# 6draft_onBoard.net
KiCad netlist of a schematic drawn in EAGLE
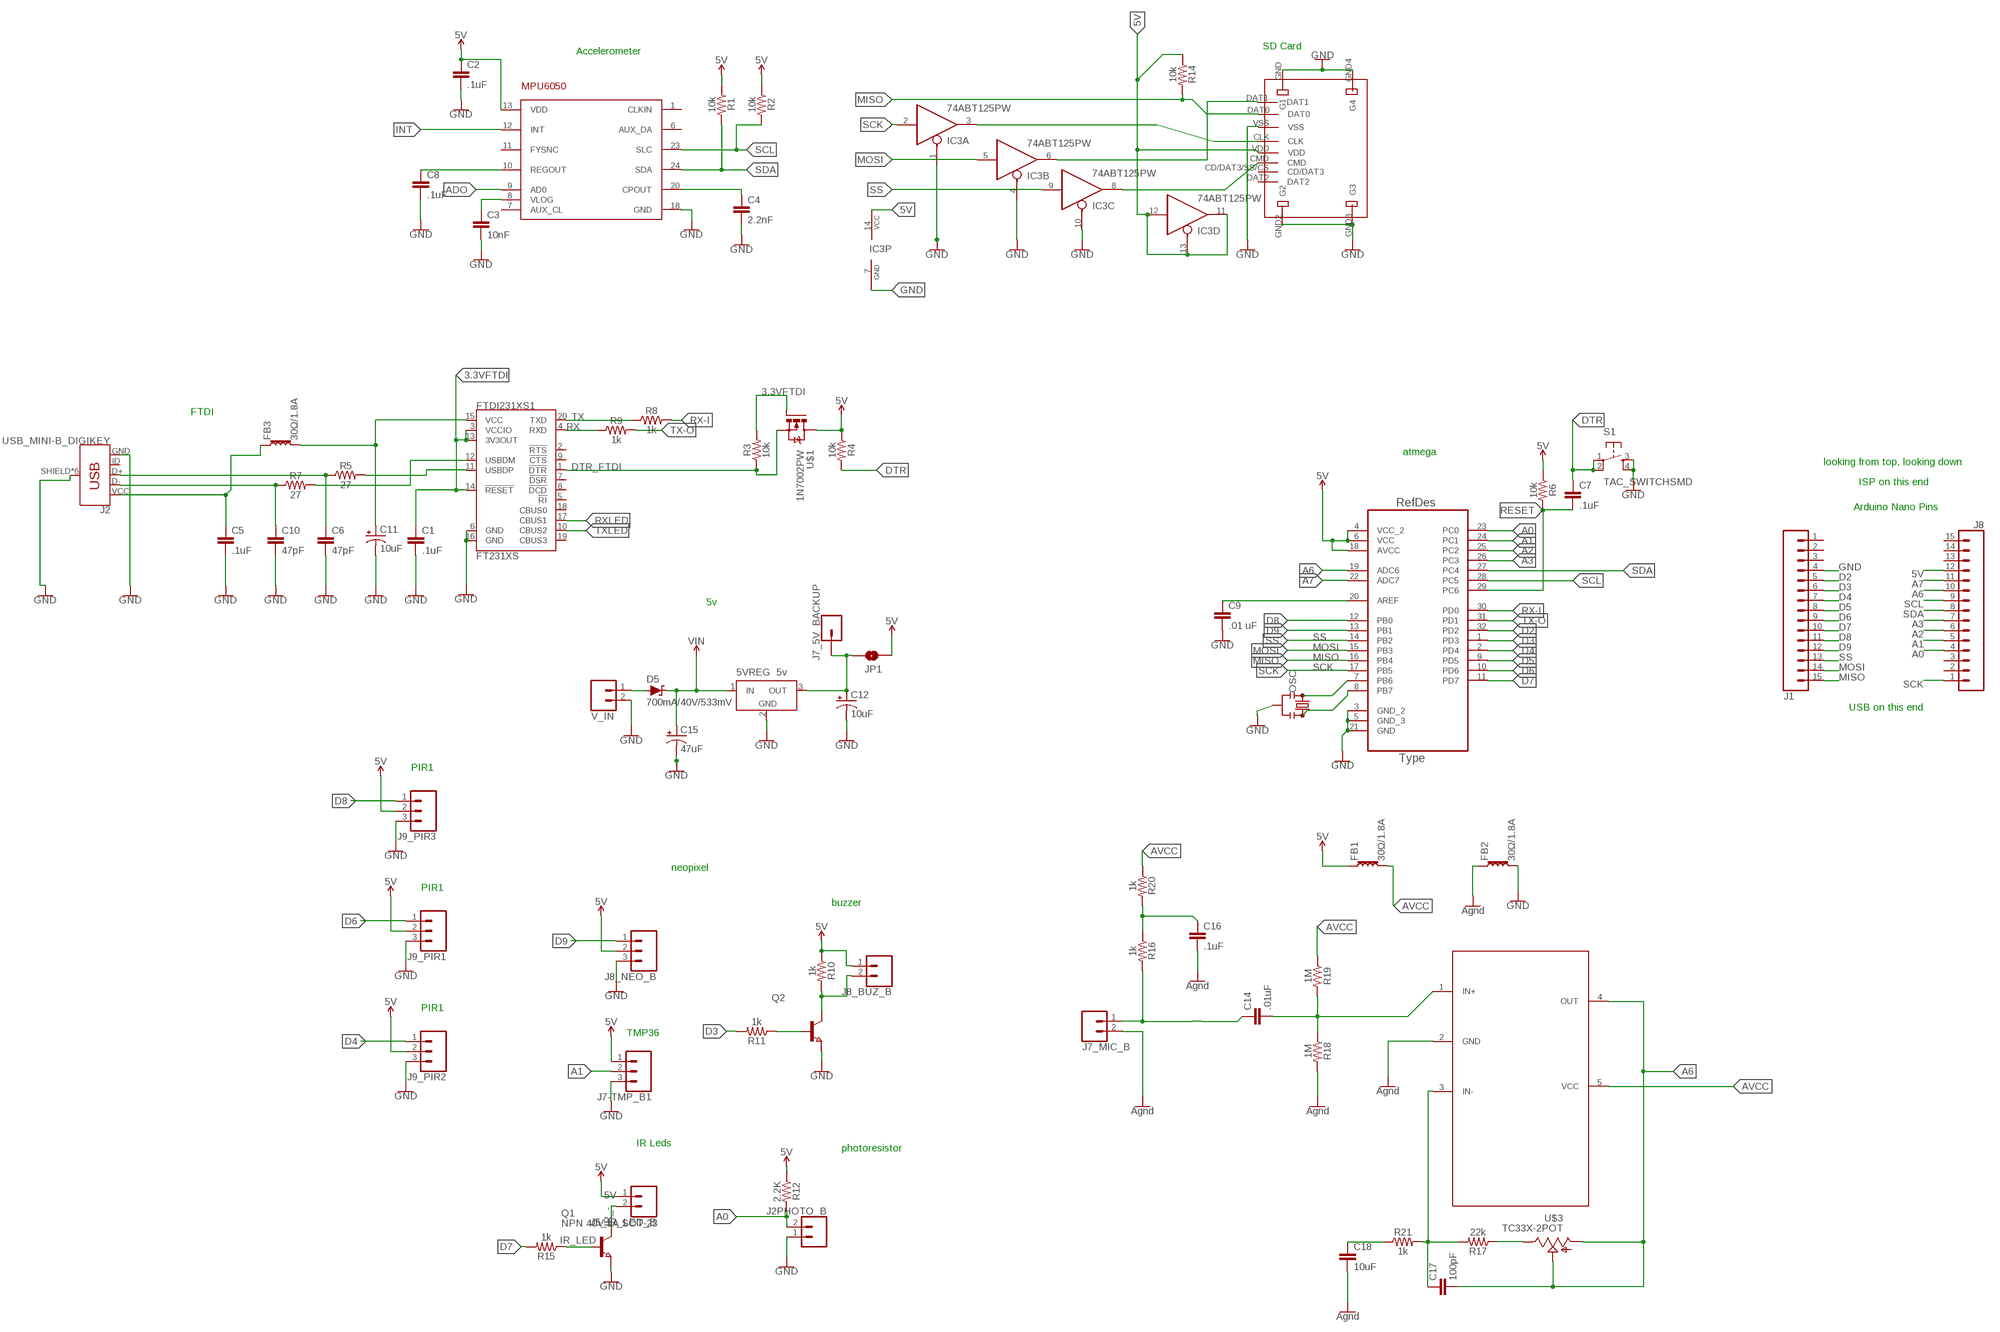
[diagram p0: schematic, sheet 1]

(export (version "E")
  (design (tool "Eeschema 10.0.6"))
  (components
    (comp (ref "5VREG")
      (value "5v")
      (footprint "eagle-import:SOT223")
      (fields (field (name "MPN") "LT1129CST-5#PBF"))
      (libsource (lib "eagle-import") (part "LT1129CST5"))
    )
    (comp (ref "ATMEGA328P-AU")
      (value "ATMEGA328P-AU")
      (footprint "eagle-import:QFP80P900X900X120-32N")
      (libsource (lib "eagle-import") (part "ATMEGA328P-AU"))
    )
    (comp (ref "C1")
      (value ".1uF")
      (footprint "eagle-import:0402-CAP")
      (libsource (lib "eagle-import") (part ".22UF-CER"))
    )
    (comp (ref "C2")
      (value ".1uF")
      (footprint "eagle-import:0402-CAP")
      (libsource (lib "eagle-import") (part ".22UF-CER"))
    )
    (comp (ref "C3")
      (value "10nF")
      (footprint "eagle-import:0402-CAP")
      (libsource (lib "eagle-import") (part ".22UF-CER"))
    )
    (comp (ref "C4")
      (value "2.2nF")
      (footprint "eagle-import:0402-CAP")
      (libsource (lib "eagle-import") (part ".22UF-CER"))
    )
    (comp (ref "C5")
      (value ".1uF")
      (footprint "eagle-import:0402-CAP")
      (libsource (lib "eagle-import") (part ".22UF-CER"))
    )
    (comp (ref "C6")
      (value "47pF")
      (footprint "eagle-import:0402-CAP")
      (libsource (lib "eagle-import") (part ".22UF-CER"))
    )
    (comp (ref "C7")
      (value ".1uF")
      (footprint "eagle-import:0402-CAP")
      (libsource (lib "eagle-import") (part ".22UF-CER"))
    )
    (comp (ref "C8")
      (value ".1uF")
      (footprint "eagle-import:0402-CAP")
      (libsource (lib "eagle-import") (part ".22UF-CER"))
    )
    (comp (ref "C9")
      (value ".01 uF")
      (footprint "eagle-import:0402-CAP")
      (libsource (lib "eagle-import") (part ".22UF-CER"))
    )
    (comp (ref "C10")
      (value "47pF")
      (footprint "eagle-import:0402-CAP")
      (libsource (lib "eagle-import") (part ".22UF-CER"))
    )
    (comp (ref "C11")
      (value "10uF")
      (footprint "eagle-import:EIA3216")
      (libsource (lib "eagle-import") (part "10UF-TANT"))
    )
    (comp (ref "C12")
      (value "10uF")
      (footprint "eagle-import:EIA3216")
      (libsource (lib "eagle-import") (part "10UF-TANT"))
    )
    (comp (ref "C14")
      (value ".01uF")
      (footprint "eagle-import:0402-CAP")
      (libsource (lib "eagle-import") (part ".22UF-CER"))
    )
    (comp (ref "C15")
      (value "47uF")
      (footprint "eagle-import:EIA3216")
      (libsource (lib "eagle-import") (part "10UF-TANT"))
    )
    (comp (ref "C16")
      (value ".1uF")
      (footprint "eagle-import:0402-CAP")
      (libsource (lib "eagle-import") (part ".22UF-CER"))
    )
    (comp (ref "C17")
      (value "100pF")
      (footprint "eagle-import:0402-CAP")
      (libsource (lib "eagle-import") (part ".22UF-CER"))
    )
    (comp (ref "C18")
      (value "10uF")
      (footprint "eagle-import:0402-CAP")
      (libsource (lib "eagle-import") (part ".22UF-CER"))
    )
    (comp (ref "D5")
      (value "700mA/40V/533mV")
      (footprint "eagle-import:SOT23-3")
      (libsource (lib "eagle-import") (part "DIODE-SCHOTTKY-ZLLS500"))
    )
    (comp (ref "FB1")
      (value "30Ω/1.8A")
      (footprint "eagle-import:0603")
      (libsource (lib "eagle-import") (part "FERRITE_BEAD-0603"))
    )
    (comp (ref "FB2")
      (value "30Ω/1.8A")
      (footprint "eagle-import:0603")
      (libsource (lib "eagle-import") (part "FERRITE_BEAD-0603"))
    )
    (comp (ref "FB3")
      (value "30Ω/1.8A")
      (footprint "eagle-import:0603")
      (libsource (lib "eagle-import") (part "FERRITE_BEAD-0603"))
    )
    (comp (ref "FTDI231XS1")
      (value "FT231XS")
      (footprint "eagle-import:SSOP20_L")
      (libsource (lib "eagle-import") (part "FT231XS"))
    )
    (comp (ref "IC3")
      (value "74ABT125PW")
      (footprint "eagle-import:TSSOP14")
      (libsource (lib "eagle-import") (part "74125PWABT"))
    )
    (comp (ref "IC4")
      (value "MAX4466KS")
      (footprint "eagle-import:SC70-5")
      (libsource (lib "eagle-import") (part "MAX4466KS"))
    )
    (comp (ref "J1")
      (value "CONN_15")
      (footprint "eagle-import:1X15")
      (libsource (lib "eagle-import") (part "CONN_15"))
    )
    (comp (ref "J2")
      (value "USB_MINI-B_DIGIKEY")
      (footprint "eagle-import:MICRO-USB-DIGIKEY-FCI2")
      (libsource (lib "eagle-import") (part "USB_MINI-B_DIGIKEY"))
    )
    (comp (ref "J2PHOTO_B")
      (value "CONN_02LOCK")
      (footprint "eagle-import:1X02_LOCK")
      (libsource (lib "eagle-import") (part "CONN_02LOCK"))
    )
    (comp (ref "J5_IR_LED_B")
      (value "CONN_02LOCK")
      (footprint "eagle-import:1X02_LOCK")
      (libsource (lib "eagle-import") (part "CONN_02LOCK"))
    )
    (comp (ref "J7-TMP_B1")
      (value "CONN_03")
      (footprint "eagle-import:1X03")
      (libsource (lib "eagle-import") (part "CONN_03"))
    )
    (comp (ref "J7_5V_BACKUP")
      (value "CONN_01")
      (footprint "eagle-import:1X01")
      (libsource (lib "eagle-import") (part "CONN_01"))
    )
    (comp (ref "J7_MIC_B")
      (value "CONN_02LOCK")
      (footprint "eagle-import:1X02_LOCK")
      (libsource (lib "eagle-import") (part "CONN_02LOCK"))
    )
    (comp (ref "J8")
      (value "CONN_15")
      (footprint "eagle-import:1X15")
      (libsource (lib "eagle-import") (part "CONN_15"))
    )
    (comp (ref "J8_BUZ_B")
      (value "CONN_02LOCK")
      (footprint "eagle-import:1X02_LOCK")
      (libsource (lib "eagle-import") (part "CONN_02LOCK"))
    )
    (comp (ref "J8_NEO_B")
      (value "CONN_03")
      (footprint "eagle-import:1X03")
      (libsource (lib "eagle-import") (part "CONN_03"))
    )
    (comp (ref "J9_PIR1")
      (value "CONN_03")
      (footprint "eagle-import:1X03")
      (libsource (lib "eagle-import") (part "CONN_03"))
    )
    (comp (ref "J9_PIR2")
      (value "CONN_03")
      (footprint "eagle-import:1X03")
      (libsource (lib "eagle-import") (part "CONN_03"))
    )
    (comp (ref "J9_PIR3")
      (value "CONN_03")
      (footprint "eagle-import:1X03")
      (libsource (lib "eagle-import") (part "CONN_03"))
    )
    (comp (ref "JP1")
      (value "JUMPER-SMT_2_NO_NO-SILK_ROUND")
      (footprint "eagle-import:SMT-JUMPER_2_NO_NO-SILK_ROUND")
      (libsource (lib "eagle-import") (part "JUMPER-SMT_2_NO_NO-SILK_ROUND"))
    )
    (comp (ref "MPU6050")
      (value "MPU-6050")
      (footprint "eagle-import:QFN24-4X4")
      (libsource (lib "eagle-import") (part "MPU-6050"))
    )
    (comp (ref "OSC")
      (value "RESONATORSMD-3.2X1.3")
      (footprint "eagle-import:RESONATOR-SMD-3.2X1.3")
      (libsource (lib "eagle-import") (part "RESONATORSMD-3.2X1.3"))
    )
    (comp (ref "Q1")
      (value "NPN 40V 1A SOT-23")
      (footprint "eagle-import:SOT23")
      (libsource (lib "eagle-import") (part "NPN-TRANSISTOR_SOT23"))
    )
    (comp (ref "Q2")
      (value "NPN-TRANSISTOR_SOT23")
      (footprint "eagle-import:SOT23")
      (libsource (lib "eagle-import") (part "NPN-TRANSISTOR_SOT23"))
    )
    (comp (ref "R1")
      (value "10k")
      (footprint "eagle-import:0603")
      (libsource (lib "eagle-import") (part "0.05OHM-0603-1/5W-1%"))
    )
    (comp (ref "R2")
      (value "10k")
      (footprint "eagle-import:0603")
      (libsource (lib "eagle-import") (part "0.05OHM-0603-1/5W-1%"))
    )
    (comp (ref "R3")
      (value "10k")
      (footprint "eagle-import:0603")
      (libsource (lib "eagle-import") (part "0.05OHM-0603-1/5W-1%"))
    )
    (comp (ref "R4")
      (value "10k")
      (footprint "eagle-import:0603")
      (libsource (lib "eagle-import") (part "0.05OHM-0603-1/5W-1%"))
    )
    (comp (ref "R5")
      (value "27")
      (footprint "eagle-import:0603")
      (libsource (lib "eagle-import") (part "0.05OHM-0603-1/5W-1%"))
    )
    (comp (ref "R6")
      (value "10k")
      (footprint "eagle-import:0603")
      (libsource (lib "eagle-import") (part "0.05OHM-0603-1/5W-1%"))
    )
    (comp (ref "R7")
      (value "27")
      (footprint "eagle-import:0603")
      (libsource (lib "eagle-import") (part "0.05OHM-0603-1/5W-1%"))
    )
    (comp (ref "R8")
      (value "1k")
      (footprint "eagle-import:0603")
      (libsource (lib "eagle-import") (part "0.05OHM-0603-1/5W-1%"))
    )
    (comp (ref "R9")
      (value "1k")
      (footprint "eagle-import:0603")
      (libsource (lib "eagle-import") (part "0.05OHM-0603-1/5W-1%"))
    )
    (comp (ref "R10")
      (value "1k")
      (footprint "eagle-import:0603")
      (libsource (lib "eagle-import") (part "0.05OHM-0603-1/5W-1%"))
    )
    (comp (ref "R11")
      (value "1k")
      (footprint "eagle-import:0603")
      (libsource (lib "eagle-import") (part "0.05OHM-0603-1/5W-1%"))
    )
    (comp (ref "R12")
      (value "2.2K")
      (footprint "eagle-import:0603")
      (libsource (lib "eagle-import") (part "0.05OHM-0603-1/5W-1%"))
    )
    (comp (ref "R14")
      (value "10k")
      (footprint "eagle-import:0603")
      (libsource (lib "eagle-import") (part "0.05OHM-0603-1/5W-1%"))
    )
    (comp (ref "R15")
      (value "1k")
      (footprint "eagle-import:0603")
      (libsource (lib "eagle-import") (part "0.05OHM-0603-1/5W-1%"))
    )
    (comp (ref "R16")
      (value "1k")
      (footprint "eagle-import:0603")
      (libsource (lib "eagle-import") (part "0.05OHM-0603-1/5W-1%"))
    )
    (comp (ref "R17")
      (value "22k")
      (footprint "eagle-import:0603")
      (libsource (lib "eagle-import") (part "0.05OHM-0603-1/5W-1%"))
    )
    (comp (ref "R18")
      (value "1M")
      (footprint "eagle-import:0603")
      (libsource (lib "eagle-import") (part "0.05OHM-0603-1/5W-1%"))
    )
    (comp (ref "R19")
      (value "1M")
      (footprint "eagle-import:0603")
      (libsource (lib "eagle-import") (part "0.05OHM-0603-1/5W-1%"))
    )
    (comp (ref "R20")
      (value "1k")
      (footprint "eagle-import:0603")
      (libsource (lib "eagle-import") (part "0.05OHM-0603-1/5W-1%"))
    )
    (comp (ref "R21")
      (value "1k")
      (footprint "eagle-import:0603")
      (libsource (lib "eagle-import") (part "0.05OHM-0603-1/5W-1%"))
    )
    (comp (ref "S1")
      (value "TAC_SWITCHSMD")
      (footprint "eagle-import:TACTILE-SWITCH-SMD")
      (libsource (lib "eagle-import") (part "TAC_SWITCHSMD"))
    )
    (comp (ref "U$1")
      (value "1N7002PW")
      (footprint "eagle-import:SOT323W_INFINEON")
      (libsource (lib "eagle-import") (part "1N7002PW"))
    )
    (comp (ref "U$2")
      (value "WM6698TR-ND_MICROSD")
      (footprint "eagle-import:MICROSD2")
      (libsource (lib "eagle-import") (part "WM6698TR-ND_MICROSD"))
    )
    (comp (ref "U$3")
      (value "TC33X-2POT")
      (footprint "eagle-import:TC33X-2")
      (libsource (lib "eagle-import") (part "TC33X-2POT"))
    )
    (comp (ref "V_IN")
      (value "CONN_02LOCK")
      (footprint "eagle-import:1X02_LOCK")
      (libsource (lib "eagle-import") (part "CONN_02LOCK"))
    )
  )
  (nets
    (net (code "1") (name "/DTR_FTDI") (class "Default")
      (node (ref "FTDI231XS1") (pin "1") (pinfunction "~{DTR}_1") (pintype "bidirectional"))
      (node (ref "R3") (pin "1") (pinfunction "1_1") (pintype "passive"))
      (node (ref "U$1") (pin "2") (pinfunction "S_2") (pintype "passive"))
    )
    (net (code "2") (name "/IR_-") (class "Default")
      (node (ref "J5_IR_LED_B") (pin "2") (pinfunction "2_2") (pintype "passive"))
      (node (ref "Q1") (pin "3") (pinfunction "C_3") (pintype "passive"))
    )
    (net (code "3") (name "/IR_LED") (class "Default")
      (node (ref "Q1") (pin "1") (pinfunction "B_1") (pintype "passive"))
      (node (ref "R15") (pin "1") (pinfunction "1_1") (pintype "passive"))
    )
    (net (code "4") (name "/RX") (class "Default")
      (node (ref "FTDI231XS1") (pin "4") (pinfunction "RXD_4") (pintype "bidirectional"))
      (node (ref "R9") (pin "1") (pinfunction "1_1") (pintype "passive"))
    )
    (net (code "5") (name "/TX") (class "Default")
      (node (ref "FTDI231XS1") (pin "20") (pinfunction "TXD_20") (pintype "bidirectional"))
      (node (ref "R8") (pin "1") (pinfunction "1_1") (pintype "passive"))
    )
    (net (code "6") (name "/VUSB") (class "Default")
      (node (ref "C11") (pin "A") (pinfunction "+_A") (pintype "passive"))
      (node (ref "C5") (pin "1") (pinfunction "1_1") (pintype "passive"))
      (node (ref "FB3") (pin "1") (pinfunction "1_1") (pintype "passive"))
      (node (ref "FB3") (pin "2") (pinfunction "2_2") (pintype "passive"))
      (node (ref "FTDI231XS1") (pin "15") (pinfunction "VCC_15") (pintype "bidirectional"))
      (node (ref "J2") (pin "VCC") (pinfunction "VBUS_VCC") (pintype "power_in"))
    )
    (net (code "7") (name "3.3VFTDI") (class "Default")
      (node (ref "C1") (pin "1") (pinfunction "1_1") (pintype "passive"))
      (node (ref "FTDI231XS1") (pin "13") (pinfunction "3V3OUT_13") (pintype "bidirectional"))
      (node (ref "FTDI231XS1") (pin "14") (pinfunction "~{RESET}_14") (pintype "bidirectional"))
      (node (ref "FTDI231XS1") (pin "3") (pinfunction "VCCIO_3") (pintype "bidirectional"))
      (node (ref "R3") (pin "2") (pinfunction "2_2") (pintype "passive"))
      (node (ref "U$1") (pin "1") (pinfunction "G_1") (pintype "passive"))
    )
    (net (code "8") (name "5V") (class "Default")
      (node (ref "ATMEGA328P-AU") (pin "18") (pinfunction "AVCC_18") (pintype "power_in"))
      (node (ref "ATMEGA328P-AU") (pin "4") (pinfunction "VCC_2_4") (pintype "power_in"))
      (node (ref "ATMEGA328P-AU") (pin "6") (pinfunction "VCC_6") (pintype "power_in"))
      (node (ref "C2") (pin "1") (pinfunction "1_1") (pintype "passive"))
      (node (ref "FB1") (pin "1") (pinfunction "1_1") (pintype "passive"))
      (node (ref "IC3") (pin "11") (pinfunction "O_11") (pintype "tri_state"))
      (node (ref "IC3") (pin "12") (pinfunction "I_12") (pintype "input"))
      (node (ref "IC3") (pin "13") (pinfunction "OE_13") (pintype "input"))
      (node (ref "IC3") (pin "14") (pinfunction "VCC_14") (pintype "power_in"))
      (node (ref "J5_IR_LED_B") (pin "1") (pinfunction "1_1") (pintype "passive"))
      (node (ref "J7-TMP_B1") (pin "1") (pinfunction "1_1") (pintype "passive"))
      (node (ref "J8") (pin "12") (pinfunction "12_12") (pintype "passive"))
      (node (ref "J8_BUZ_B") (pin "1") (pinfunction "1_1") (pintype "passive"))
      (node (ref "J8_NEO_B") (pin "2") (pinfunction "2_2") (pintype "passive"))
      (node (ref "J9_PIR1") (pin "2") (pinfunction "2_2") (pintype "passive"))
      (node (ref "J9_PIR2") (pin "2") (pinfunction "2_2") (pintype "passive"))
      (node (ref "J9_PIR3") (pin "2") (pinfunction "2_2") (pintype "passive"))
      (node (ref "JP1") (pin "1") (pinfunction "1_1") (pintype "passive"))
      (node (ref "MPU6050") (pin "13") (pinfunction "VDD_13") (pintype "bidirectional"))
      (node (ref "R1") (pin "1") (pinfunction "1_1") (pintype "passive"))
      (node (ref "R10") (pin "1") (pinfunction "1_1") (pintype "passive"))
      (node (ref "R12") (pin "1") (pinfunction "1_1") (pintype "passive"))
      (node (ref "R14") (pin "1") (pinfunction "1_1") (pintype "passive"))
      (node (ref "R2") (pin "1") (pinfunction "1_1") (pintype "passive"))
      (node (ref "R4") (pin "1") (pinfunction "1_1") (pintype "passive"))
      (node (ref "R6") (pin "1") (pinfunction "1_1") (pintype "passive"))
      (node (ref "U$1") (pin "3") (pinfunction "D_3") (pintype "passive"))
      (node (ref "U$2") (pin "VDD") (pinfunction "VDD_VDD") (pintype "bidirectional"))
    )
    (net (code "9") (name "A0") (class "Default")
      (node (ref "ATMEGA328P-AU") (pin "23") (pinfunction "PC0_23") (pintype "bidirectional"))
      (node (ref "J2PHOTO_B") (pin "2") (pinfunction "2_2") (pintype "passive"))
      (node (ref "J8") (pin "4") (pinfunction "4_4") (pintype "passive"))
      (node (ref "R12") (pin "2") (pinfunction "2_2") (pintype "passive"))
    )
    (net (code "10") (name "A1") (class "Default")
      (node (ref "ATMEGA328P-AU") (pin "24") (pinfunction "PC1_24") (pintype "bidirectional"))
      (node (ref "J7-TMP_B1") (pin "2") (pinfunction "2_2") (pintype "passive"))
      (node (ref "J8") (pin "5") (pinfunction "5_5") (pintype "passive"))
    )
    (net (code "11") (name "A2") (class "Default")
      (node (ref "ATMEGA328P-AU") (pin "25") (pinfunction "PC2_25") (pintype "bidirectional"))
      (node (ref "J8") (pin "6") (pinfunction "6_6") (pintype "passive"))
    )
    (net (code "12") (name "A3") (class "Default")
      (node (ref "ATMEGA328P-AU") (pin "26") (pinfunction "PC3_26") (pintype "bidirectional"))
      (node (ref "J8") (pin "7") (pinfunction "7_7") (pintype "passive"))
    )
    (net (code "13") (name "A6") (class "Default")
      (node (ref "ATMEGA328P-AU") (pin "19") (pinfunction "ADC6_19") (pintype "input"))
      (node (ref "C17") (pin "2") (pinfunction "2_2") (pintype "passive"))
      (node (ref "IC4") (pin "4") (pinfunction "OUT_4") (pintype "bidirectional"))
      (node (ref "J8") (pin "10") (pinfunction "10_10") (pintype "passive"))
      (node (ref "U$3") (pin "2") (pinfunction "2_2") (pintype "passive"))
      (node (ref "U$3") (pin "3") (pinfunction "3_3") (pintype "passive"))
    )
    (net (code "14") (name "A7") (class "Default")
      (node (ref "ATMEGA328P-AU") (pin "22") (pinfunction "ADC7_22") (pintype "input"))
      (node (ref "J8") (pin "11") (pinfunction "11_11") (pintype "passive"))
    )
    (net (code "15") (name "ADO") (class "Default")
      (node (ref "MPU6050") (pin "9") (pinfunction "AD0_9") (pintype "bidirectional"))
    )
    (net (code "16") (name "AVCC") (class "Default")
      (node (ref "FB1") (pin "2") (pinfunction "2_2") (pintype "passive"))
      (node (ref "IC4") (pin "5") (pinfunction "VCC_5") (pintype "bidirectional"))
      (node (ref "R19") (pin "1") (pinfunction "1_1") (pintype "passive"))
      (node (ref "R20") (pin "1") (pinfunction "1_1") (pintype "passive"))
    )
    (net (code "17") (name "D2") (class "Default")
      (node (ref "ATMEGA328P-AU") (pin "32") (pinfunction "PD2_32") (pintype "bidirectional"))
      (node (ref "J1") (pin "5") (pinfunction "5_5") (pintype "passive"))
    )
    (net (code "18") (name "D3") (class "Default")
      (node (ref "ATMEGA328P-AU") (pin "1") (pinfunction "PD3_1") (pintype "bidirectional"))
      (node (ref "J1") (pin "6") (pinfunction "6_6") (pintype "passive"))
      (node (ref "R11") (pin "2") (pinfunction "2_2") (pintype "passive"))
    )
    (net (code "19") (name "D4") (class "Default")
      (node (ref "ATMEGA328P-AU") (pin "2") (pinfunction "PD4_2") (pintype "bidirectional"))
      (node (ref "J1") (pin "7") (pinfunction "7_7") (pintype "passive"))
      (node (ref "J9_PIR2") (pin "1") (pinfunction "1_1") (pintype "passive"))
    )
    (net (code "20") (name "D5") (class "Default")
      (node (ref "ATMEGA328P-AU") (pin "9") (pinfunction "PD5_9") (pintype "bidirectional"))
      (node (ref "J1") (pin "8") (pinfunction "8_8") (pintype "passive"))
    )
    (net (code "21") (name "D6") (class "Default")
      (node (ref "ATMEGA328P-AU") (pin "10") (pinfunction "PD6_10") (pintype "bidirectional"))
      (node (ref "J1") (pin "9") (pinfunction "9_9") (pintype "passive"))
      (node (ref "J9_PIR1") (pin "1") (pinfunction "1_1") (pintype "passive"))
    )
    (net (code "22") (name "D7") (class "Default")
      (node (ref "ATMEGA328P-AU") (pin "11") (pinfunction "PD7_11") (pintype "bidirectional"))
      (node (ref "J1") (pin "10") (pinfunction "10_10") (pintype "passive"))
      (node (ref "R15") (pin "2") (pinfunction "2_2") (pintype "passive"))
    )
    (net (code "23") (name "D8") (class "Default")
      (node (ref "ATMEGA328P-AU") (pin "12") (pinfunction "PB0_12") (pintype "bidirectional"))
      (node (ref "J1") (pin "11") (pinfunction "11_11") (pintype "passive"))
      (node (ref "J9_PIR3") (pin "1") (pinfunction "1_1") (pintype "passive"))
    )
    (net (code "24") (name "D9") (class "Default")
      (node (ref "ATMEGA328P-AU") (pin "13") (pinfunction "PB1_13") (pintype "bidirectional"))
      (node (ref "J1") (pin "12") (pinfunction "12_12") (pintype "passive"))
      (node (ref "J8_NEO_B") (pin "1") (pinfunction "1_1") (pintype "passive"))
    )
    (net (code "25") (name "DTR") (class "Default")
      (node (ref "C7") (pin "1") (pinfunction "1_1") (pintype "passive"))
      (node (ref "R4") (pin "2") (pinfunction "2_2") (pintype "passive"))
      (node (ref "S1") (pin "1") (pinfunction "1_1") (pintype "passive"))
      (node (ref "S1") (pin "2") (pinfunction "2_2") (pintype "passive"))
    )
    (net (code "26") (name "GND") (class "Default")
      (node (ref "5VREG") (pin "2") (pinfunction "GND_2") (pintype "power_in"))
      (node (ref "ATMEGA328P-AU") (pin "21") (pinfunction "GND_21") (pintype "passive"))
      (node (ref "ATMEGA328P-AU") (pin "3") (pinfunction "GND_2_3") (pintype "passive"))
      (node (ref "ATMEGA328P-AU") (pin "5") (pinfunction "GND_3_5") (pintype "passive"))
      (node (ref "C1") (pin "2") (pinfunction "2_2") (pintype "passive"))
      (node (ref "C10") (pin "2") (pinfunction "2_2") (pintype "passive"))
      (node (ref "C11") (pin "C") (pinfunction "-_C") (pintype "passive"))
      (node (ref "C12") (pin "C") (pinfunction "-_C") (pintype "passive"))
      (node (ref "C15") (pin "C") (pinfunction "-_C") (pintype "passive"))
      (node (ref "C16") (pin "2") (pinfunction "2_2") (pintype "passive"))
      (node (ref "C18") (pin "2") (pinfunction "2_2") (pintype "passive"))
      (node (ref "C2") (pin "2") (pinfunction "2_2") (pintype "passive"))
      (node (ref "C3") (pin "2") (pinfunction "2_2") (pintype "passive"))
      (node (ref "C4") (pin "2") (pinfunction "2_2") (pintype "passive"))
      (node (ref "C5") (pin "2") (pinfunction "2_2") (pintype "passive"))
      (node (ref "C6") (pin "2") (pinfunction "2_2") (pintype "passive"))
      (node (ref "C8") (pin "2") (pinfunction "2_2") (pintype "passive"))
      (node (ref "C9") (pin "2") (pinfunction "2_2") (pintype "passive"))
      (node (ref "FB2") (pin "1") (pinfunction "1_1") (pintype "passive"))
      (node (ref "FB2") (pin "2") (pinfunction "2_2") (pintype "passive"))
      (node (ref "FTDI231XS1") (pin "16") (pinfunction "GND_16") (pintype "bidirectional"))
      (node (ref "FTDI231XS1") (pin "6") (pinfunction "GND_6") (pintype "bidirectional"))
      (node (ref "IC3") (pin "1") (pinfunction "OE_1") (pintype "input"))
      (node (ref "IC3") (pin "10") (pinfunction "OE_10") (pintype "input"))
      (node (ref "IC3") (pin "4") (pinfunction "OE_4") (pintype "input"))
      (node (ref "IC3") (pin "7") (pinfunction "GND_7") (pintype "power_in"))
      (node (ref "IC4") (pin "2") (pinfunction "GND_2") (pintype "bidirectional"))
      (node (ref "J1") (pin "4") (pinfunction "4_4") (pintype "passive"))
      (node (ref "J2") (pin "GND") (pinfunction "GND_GND") (pintype "power_in"))
      (node (ref "J2") (pin "SHIELD") (pinfunction "SHIELD_SHIELD") (pintype "bidirectional"))
      (node (ref "J2") (pin "SHIELD1") (pinfunction "SHIELD_SHIELD1") (pintype "bidirectional"))
      (node (ref "J2") (pin "SHIELD2") (pinfunction "SHIELD_SHIELD2") (pintype "bidirectional"))
      (node (ref "J2") (pin "SHIELD3") (pinfunction "SHIELD_SHIELD3") (pintype "bidirectional"))
      (node (ref "J2") (pin "SHIELD4") (pinfunction "SHIELD_SHIELD4") (pintype "bidirectional"))
      (node (ref "J2") (pin "SHIELD5") (pinfunction "SHIELD_SHIELD5") (pintype "bidirectional"))
      (node (ref "J2PHOTO_B") (pin "1") (pinfunction "1_1") (pintype "passive"))
      (node (ref "J7-TMP_B1") (pin "3") (pinfunction "3_3") (pintype "passive"))
      (node (ref "J7_MIC_B") (pin "2") (pinfunction "2_2") (pintype "passive"))
      (node (ref "J8_NEO_B") (pin "3") (pinfunction "3_3") (pintype "passive"))
      (node (ref "J9_PIR1") (pin "3") (pinfunction "3_3") (pintype "passive"))
      (node (ref "J9_PIR2") (pin "3") (pinfunction "3_3") (pintype "passive"))
      (node (ref "J9_PIR3") (pin "3") (pinfunction "3_3") (pintype "passive"))
      (node (ref "MPU6050") (pin "18") (pinfunction "GND_18") (pintype "bidirectional"))
      (node (ref "OSC") (pin "2") (pinfunction "2_2") (pintype "passive"))
      (node (ref "Q1") (pin "2") (pinfunction "E_2") (pintype "passive"))
      (node (ref "Q2") (pin "2") (pinfunction "E_2") (pintype "passive"))
      (node (ref "R18") (pin "2") (pinfunction "2_2") (pintype "passive"))
      (node (ref "S1") (pin "3") (pinfunction "3_3") (pintype "passive"))
      (node (ref "S1") (pin "4") (pinfunction "4_4") (pintype "passive"))
      (node (ref "U$2") (pin "GND") (pinfunction "G1_GND") (pintype "bidirectional"))
      (node (ref "U$2") (pin "GND2") (pinfunction "G2_GND2") (pintype "bidirectional"))
      (node (ref "U$2") (pin "GND3") (pinfunction "G3_GND3") (pintype "bidirectional"))
      (node (ref "U$2") (pin "GND4") (pinfunction "G4_GND4") (pintype "bidirectional"))
      (node (ref "U$2") (pin "VSS") (pinfunction "VSS_VSS") (pintype "bidirectional"))
      (node (ref "V_IN") (pin "2") (pinfunction "2_2") (pintype "passive"))
    )
    (net (code "27") (name "INT") (class "Default")
      (node (ref "MPU6050") (pin "12") (pinfunction "INT_12") (pintype "bidirectional"))
    )
    (net (code "28") (name "MISO") (class "Default")
      (node (ref "ATMEGA328P-AU") (pin "16") (pinfunction "PB4_16") (pintype "bidirectional"))
      (node (ref "J1") (pin "15") (pinfunction "15_15") (pintype "passive"))
      (node (ref "R14") (pin "2") (pinfunction "2_2") (pintype "passive"))
      (node (ref "U$2") (pin "DAT0") (pinfunction "DAT0_DAT0") (pintype "bidirectional"))
    )
    (net (code "29") (name "MOSI") (class "Default")
      (node (ref "ATMEGA328P-AU") (pin "15") (pinfunction "PB3_15") (pintype "bidirectional"))
      (node (ref "IC3") (pin "5") (pinfunction "I_5") (pintype "input"))
      (node (ref "J1") (pin "14") (pinfunction "14_14") (pintype "passive"))
    )
    (net (code "30") (name "Net-(5VREGA-OUT)") (class "Default")
      (node (ref "5VREG") (pin "3") (pinfunction "OUT_3") (pintype "output"))
      (node (ref "C12") (pin "A") (pinfunction "+_A") (pintype "passive"))
      (node (ref "J7_5V_BACKUP") (pin "1") (pinfunction "1_1") (pintype "passive"))
      (node (ref "JP1") (pin "2") (pinfunction "2_2") (pintype "passive"))
    )
    (net (code "31") (name "Net-(ATMEGA328P-AU-AREF)") (class "Default")
      (node (ref "ATMEGA328P-AU") (pin "20") (pinfunction "AREF_20") (pintype "input"))
      (node (ref "C9") (pin "1") (pinfunction "1_1") (pintype "passive"))
    )
    (net (code "32") (name "Net-(ATMEGA328P-AU-PB6)") (class "Default")
      (node (ref "ATMEGA328P-AU") (pin "7") (pinfunction "PB6_7") (pintype "bidirectional"))
      (node (ref "OSC") (pin "1") (pinfunction "1_1") (pintype "passive"))
    )
    (net (code "33") (name "Net-(ATMEGA328P-AU-PB7)") (class "Default")
      (node (ref "ATMEGA328P-AU") (pin "8") (pinfunction "PB7_8") (pintype "bidirectional"))
      (node (ref "OSC") (pin "3") (pinfunction "3_3") (pintype "passive"))
    )
    (net (code "34") (name "Net-(C6-Pad1)") (class "Default")
      (node (ref "C6") (pin "1") (pinfunction "1_1") (pintype "passive"))
      (node (ref "J2") (pin "D+") (pinfunction "D+_D+") (pintype "bidirectional"))
      (node (ref "R5") (pin "1") (pinfunction "1_1") (pintype "passive"))
    )
    (net (code "35") (name "Net-(C10-Pad1)") (class "Default")
      (node (ref "C10") (pin "1") (pinfunction "1_1") (pintype "passive"))
      (node (ref "J2") (pin "D-") (pinfunction "D-_D-") (pintype "bidirectional"))
      (node (ref "R7") (pin "1") (pinfunction "1_1") (pintype "passive"))
    )
    (net (code "36") (name "Net-(C14-Pad1)") (class "Default")
      (node (ref "C14") (pin "1") (pinfunction "1_1") (pintype "passive"))
      (node (ref "J7_MIC_B") (pin "1") (pinfunction "1_1") (pintype "passive"))
      (node (ref "R16") (pin "2") (pinfunction "2_2") (pintype "passive"))
    )
    (net (code "37") (name "Net-(C16-Pad1)") (class "Default")
      (node (ref "C16") (pin "1") (pinfunction "1_1") (pintype "passive"))
      (node (ref "R16") (pin "1") (pinfunction "1_1") (pintype "passive"))
      (node (ref "R20") (pin "2") (pinfunction "2_2") (pintype "passive"))
    )
    (net (code "38") (name "Net-(C18-Pad1)") (class "Default")
      (node (ref "C18") (pin "1") (pinfunction "1_1") (pintype "passive"))
      (node (ref "R21") (pin "1") (pinfunction "1_1") (pintype "passive"))
    )
    (net (code "39") (name "Net-(D5-A)") (class "Default")
      (node (ref "D5") (pin "1") (pinfunction "A_1") (pintype "passive"))
      (node (ref "V_IN") (pin "1") (pinfunction "1_1") (pintype "passive"))
    )
    (net (code "40") (name "Net-(FTDI231XS1-USBDM)") (class "Default")
      (node (ref "FTDI231XS1") (pin "12") (pinfunction "USBDM_12") (pintype "bidirectional"))
      (node (ref "R7") (pin "2") (pinfunction "2_2") (pintype "passive"))
    )
    (net (code "41") (name "Net-(FTDI231XS1-USBDP)") (class "Default")
      (node (ref "FTDI231XS1") (pin "11") (pinfunction "USBDP_11") (pintype "bidirectional"))
      (node (ref "R5") (pin "2") (pinfunction "2_2") (pintype "passive"))
    )
    (net (code "42") (name "Net-(IC3A-O)") (class "Default")
      (node (ref "IC3") (pin "3") (pinfunction "O_3") (pintype "tri_state"))
      (node (ref "U$2") (pin "CLK") (pinfunction "CLK_CLK") (pintype "bidirectional"))
    )
    (net (code "43") (name "Net-(IC3B-O)") (class "Default")
      (node (ref "IC3") (pin "6") (pinfunction "O_6") (pintype "tri_state"))
      (node (ref "U$2") (pin "DAT1") (pinfunction "DAT1_DAT1") (pintype "bidirectional"))
    )
    (net (code "44") (name "Net-(IC3C-O)") (class "Default")
      (node (ref "IC3") (pin "8") (pinfunction "O_8") (pintype "tri_state"))
      (node (ref "U$2") (pin "CMD") (pinfunction "CMD_CMD") (pintype "bidirectional"))
    )
    (net (code "45") (name "Net-(IC4-IN+)") (class "Default")
      (node (ref "C14") (pin "2") (pinfunction "2_2") (pintype "passive"))
      (node (ref "IC4") (pin "1") (pinfunction "IN+_1") (pintype "bidirectional"))
      (node (ref "R18") (pin "1") (pinfunction "1_1") (pintype "passive"))
      (node (ref "R19") (pin "2") (pinfunction "2_2") (pintype "passive"))
    )
    (net (code "46") (name "Net-(IC4-IN-)") (class "Default")
      (node (ref "C17") (pin "1") (pinfunction "1_1") (pintype "passive"))
      (node (ref "IC4") (pin "3") (pinfunction "IN-_3") (pintype "bidirectional"))
      (node (ref "R17") (pin "2") (pinfunction "2_2") (pintype "passive"))
      (node (ref "R21") (pin "2") (pinfunction "2_2") (pintype "passive"))
    )
    (net (code "47") (name "Net-(MPU6050-CPOUT)") (class "Default")
      (node (ref "C4") (pin "1") (pinfunction "1_1") (pintype "passive"))
      (node (ref "MPU6050") (pin "20") (pinfunction "CPOUT_20") (pintype "bidirectional"))
    )
    (net (code "48") (name "Net-(MPU6050-REGOUT)") (class "Default")
      (node (ref "C8") (pin "1") (pinfunction "1_1") (pintype "passive"))
      (node (ref "MPU6050") (pin "10") (pinfunction "REGOUT_10") (pintype "bidirectional"))
    )
    (net (code "49") (name "Net-(MPU6050-VLOG)") (class "Default")
      (node (ref "C3") (pin "1") (pinfunction "1_1") (pintype "passive"))
      (node (ref "MPU6050") (pin "8") (pinfunction "VLOG_8") (pintype "bidirectional"))
    )
    (net (code "50") (name "Net-(Q2-B)") (class "Default")
      (node (ref "Q2") (pin "1") (pinfunction "B_1") (pintype "passive"))
      (node (ref "R11") (pin "1") (pinfunction "1_1") (pintype "passive"))
    )
    (net (code "51") (name "Net-(Q2-C)") (class "Default")
      (node (ref "J8_BUZ_B") (pin "2") (pinfunction "2_2") (pintype "passive"))
      (node (ref "Q2") (pin "3") (pinfunction "C_3") (pintype "passive"))
      (node (ref "R10") (pin "2") (pinfunction "2_2") (pintype "passive"))
    )
    (net (code "52") (name "Net-(R17-Pad1)") (class "Default")
      (node (ref "R17") (pin "1") (pinfunction "1_1") (pintype "passive"))
      (node (ref "U$3") (pin "1") (pinfunction "1_1") (pintype "passive"))
    )
    (net (code "53") (name "RESET") (class "Default")
      (node (ref "ATMEGA328P-AU") (pin "29") (pinfunction "PC6_29") (pintype "bidirectional"))
      (node (ref "C7") (pin "2") (pinfunction "2_2") (pintype "passive"))
      (node (ref "R6") (pin "2") (pinfunction "2_2") (pintype "passive"))
    )
    (net (code "54") (name "RX-I") (class "Default")
      (node (ref "ATMEGA328P-AU") (pin "30") (pinfunction "PD0_30") (pintype "bidirectional"))
      (node (ref "R8") (pin "2") (pinfunction "2_2") (pintype "passive"))
    )
    (net (code "55") (name "RXLED") (class "Default")
      (node (ref "FTDI231XS1") (pin "17") (pinfunction "CBUS1_17") (pintype "bidirectional"))
    )
    (net (code "56") (name "SCK") (class "Default")
      (node (ref "ATMEGA328P-AU") (pin "17") (pinfunction "PB5_17") (pintype "bidirectional"))
      (node (ref "IC3") (pin "2") (pinfunction "I_2") (pintype "input"))
      (node (ref "J8") (pin "1") (pinfunction "1_1") (pintype "passive"))
    )
    (net (code "57") (name "SCL") (class "Default")
      (node (ref "ATMEGA328P-AU") (pin "28") (pinfunction "PC5_28") (pintype "bidirectional"))
      (node (ref "J8") (pin "9") (pinfunction "9_9") (pintype "passive"))
      (node (ref "MPU6050") (pin "23") (pinfunction "SLC_23") (pintype "bidirectional"))
      (node (ref "R2") (pin "2") (pinfunction "2_2") (pintype "passive"))
    )
    (net (code "58") (name "SDA") (class "Default")
      (node (ref "ATMEGA328P-AU") (pin "27") (pinfunction "PC4_27") (pintype "bidirectional"))
      (node (ref "J8") (pin "8") (pinfunction "8_8") (pintype "passive"))
      (node (ref "MPU6050") (pin "24") (pinfunction "SDA_24") (pintype "bidirectional"))
      (node (ref "R1") (pin "2") (pinfunction "2_2") (pintype "passive"))
    )
    (net (code "59") (name "SS") (class "Default")
      (node (ref "ATMEGA328P-AU") (pin "14") (pinfunction "PB2_14") (pintype "bidirectional"))
      (node (ref "IC3") (pin "9") (pinfunction "I_9") (pintype "input"))
      (node (ref "J1") (pin "13") (pinfunction "13_13") (pintype "passive"))
    )
    (net (code "60") (name "TX-O") (class "Default")
      (node (ref "ATMEGA328P-AU") (pin "31") (pinfunction "PD1_31") (pintype "bidirectional"))
      (node (ref "R9") (pin "2") (pinfunction "2_2") (pintype "passive"))
    )
    (net (code "61") (name "TXLED") (class "Default")
      (node (ref "FTDI231XS1") (pin "10") (pinfunction "CBUS2_10") (pintype "bidirectional"))
    )
    (net (code "62") (name "VIN") (class "Default")
      (node (ref "5VREG") (pin "1") (pinfunction "IN_1") (pintype "input"))
      (node (ref "C15") (pin "A") (pinfunction "+_A") (pintype "passive"))
      (node (ref "D5") (pin "3") (pinfunction "C_3") (pintype "passive"))
    )
    (net (code "63") (name "unconnected-(FTDI231XS1-CBUS0-Pad18)") (class "Default")
      (node (ref "FTDI231XS1") (pin "18") (pinfunction "CBUS0_18") (pintype "bidirectional"))
    )
    (net (code "64") (name "unconnected-(FTDI231XS1-CBUS3-Pad19)") (class "Default")
      (node (ref "FTDI231XS1") (pin "19") (pinfunction "CBUS3_19") (pintype "bidirectional"))
    )
    (net (code "65") (name "unconnected-(FTDI231XS1-~{CTS}-Pad9)") (class "Default")
      (node (ref "FTDI231XS1") (pin "9") (pinfunction "~{CTS}_9") (pintype "bidirectional"))
    )
    (net (code "66") (name "unconnected-(FTDI231XS1-~{DCD}-Pad8)") (class "Default")
      (node (ref "FTDI231XS1") (pin "8") (pinfunction "~{DCD}_8") (pintype "bidirectional"))
    )
    (net (code "67") (name "unconnected-(FTDI231XS1-~{DSR}-Pad7)") (class "Default")
      (node (ref "FTDI231XS1") (pin "7") (pinfunction "~{DSR}_7") (pintype "bidirectional"))
    )
    (net (code "68") (name "unconnected-(FTDI231XS1-~{RI}-Pad5)") (class "Default")
      (node (ref "FTDI231XS1") (pin "5") (pinfunction "~{RI}_5") (pintype "bidirectional"))
    )
    (net (code "69") (name "unconnected-(FTDI231XS1-~{RTS}-Pad2)") (class "Default")
      (node (ref "FTDI231XS1") (pin "2") (pinfunction "~{RTS}_2") (pintype "bidirectional"))
    )
    (net (code "70") (name "unconnected-(J1-Pad1)") (class "Default")
      (node (ref "J1") (pin "1") (pinfunction "1_1") (pintype "passive"))
    )
    (net (code "71") (name "unconnected-(J1-Pad2)") (class "Default")
      (node (ref "J1") (pin "2") (pinfunction "2_2") (pintype "passive"))
    )
    (net (code "72") (name "unconnected-(J1-Pad3)") (class "Default")
      (node (ref "J1") (pin "3") (pinfunction "3_3") (pintype "passive"))
    )
    (net (code "73") (name "unconnected-(J2-PadID)") (class "Default")
      (node (ref "J2") (pin "ID") (pinfunction "ID_ID") (pintype "bidirectional"))
    )
    (net (code "74") (name "unconnected-(J8-Pad2)") (class "Default")
      (node (ref "J8") (pin "2") (pinfunction "2_2") (pintype "passive"))
    )
    (net (code "75") (name "unconnected-(J8-Pad3)") (class "Default")
      (node (ref "J8") (pin "3") (pinfunction "3_3") (pintype "passive"))
    )
    (net (code "76") (name "unconnected-(J8-Pad13)") (class "Default")
      (node (ref "J8") (pin "13") (pinfunction "13_13") (pintype "passive"))
    )
    (net (code "77") (name "unconnected-(J8-Pad14)") (class "Default")
      (node (ref "J8") (pin "14") (pinfunction "14_14") (pintype "passive"))
    )
    (net (code "78") (name "unconnected-(J8-Pad15)") (class "Default")
      (node (ref "J8") (pin "15") (pinfunction "15_15") (pintype "passive"))
    )
    (net (code "79") (name "unconnected-(MPU6050-AUX_CL-Pad7)") (class "Default")
      (node (ref "MPU6050") (pin "7") (pinfunction "AUX_CL_7") (pintype "bidirectional"))
    )
    (net (code "80") (name "unconnected-(MPU6050-AUX_DA-Pad6)") (class "Default")
      (node (ref "MPU6050") (pin "6") (pinfunction "AUX_DA_6") (pintype "bidirectional"))
    )
    (net (code "81") (name "unconnected-(MPU6050-CLKIN-Pad1)") (class "Default")
      (node (ref "MPU6050") (pin "1") (pinfunction "CLKIN_1") (pintype "bidirectional"))
    )
    (net (code "82") (name "unconnected-(MPU6050-FYSNC-Pad11)") (class "Default")
      (node (ref "MPU6050") (pin "11") (pinfunction "FYSNC_11") (pintype "bidirectional"))
    )
    (net (code "83") (name "unconnected-(U$2-CD{slash}DAT3-PadCD{slash}DAT3{slash}SS{slash}CS)") (class "Default")
      (node (ref "U$2") (pin "CD/DAT3/SS/CS") (pinfunction "CD/DAT3_CD/DAT3/SS/CS") (pintype "bidirectional"))
    )
    (net (code "84") (name "unconnected-(U$2-PadDAT2)") (class "Default")
      (node (ref "U$2") (pin "DAT2") (pinfunction "DAT2_DAT2") (pintype "bidirectional"))
    )
  )
)
